# environode_display.net
KiCad netlist of a schematic drawn in EAGLE
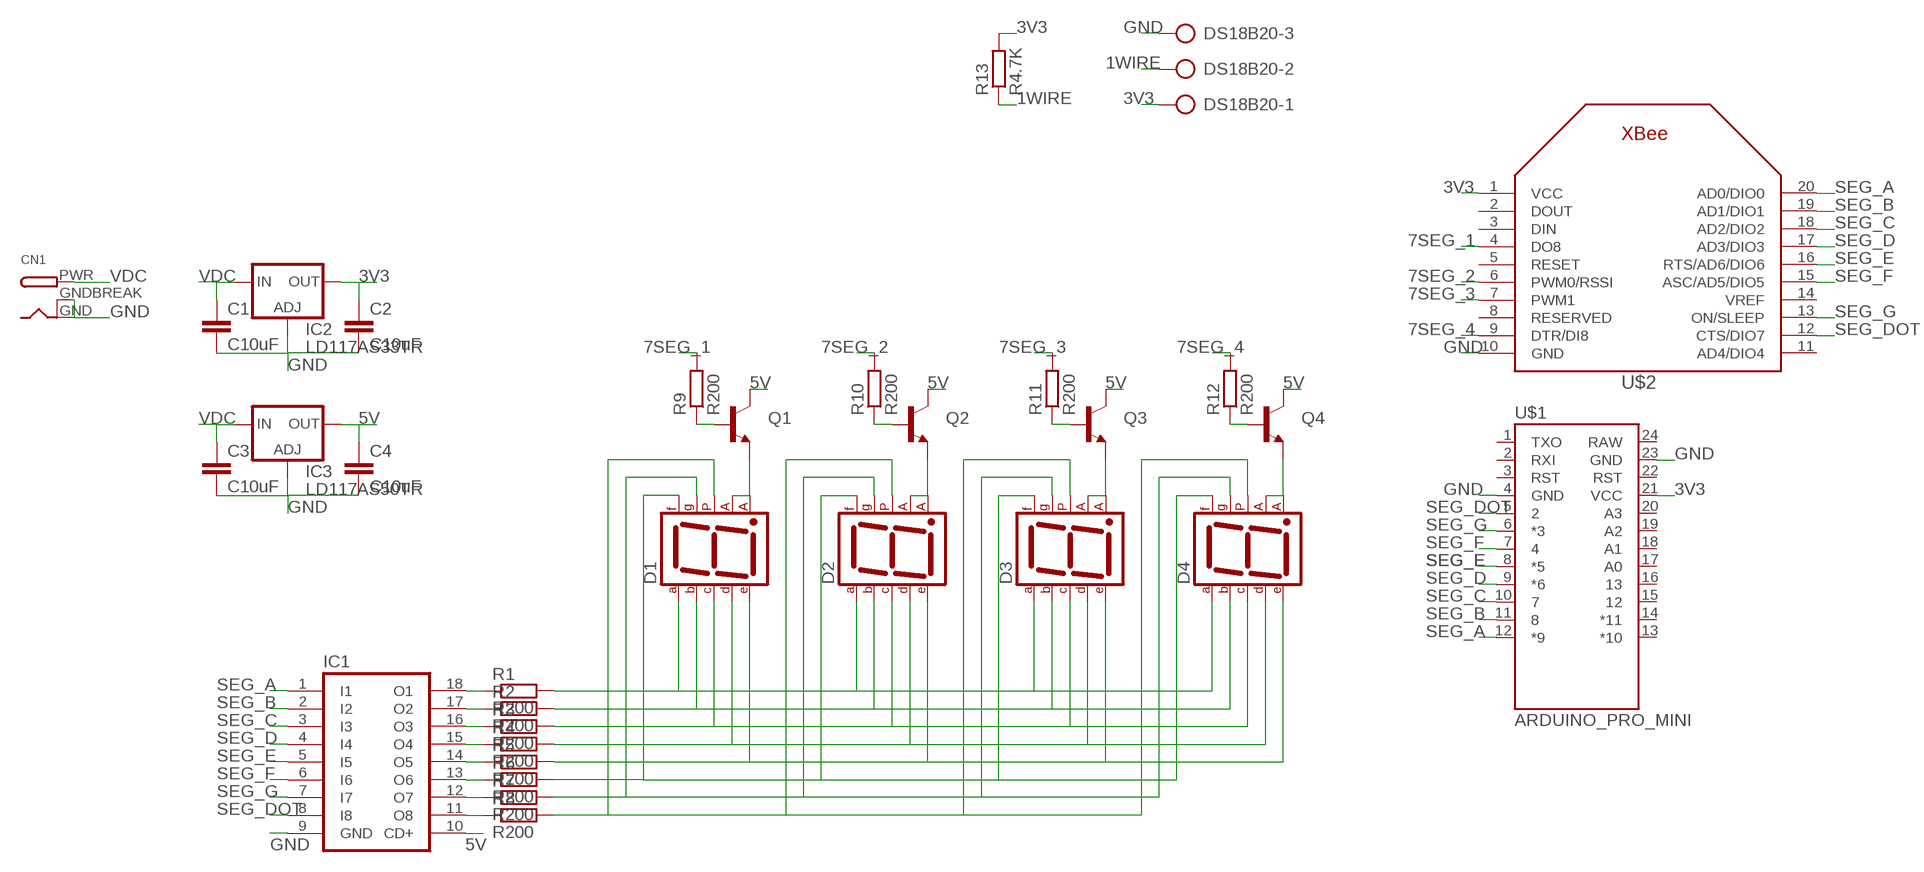
[diagram p0: schematic, sheet 1]

(export (version "E")
  (design (tool "Eeschema 10.0.6"))
  (components
    (comp (ref "C1")
      (value "C10uF")
      (footprint "eagle-import:C0805")
      (libsource (lib "eagle-import") (part "C-EUC0805"))
    )
    (comp (ref "C2")
      (value "C10uF")
      (footprint "eagle-import:C0805")
      (libsource (lib "eagle-import") (part "C-EUC0805"))
    )
    (comp (ref "C3")
      (value "C10uF")
      (footprint "eagle-import:C0805")
      (libsource (lib "eagle-import") (part "C-EUC0805"))
    )
    (comp (ref "C4")
      (value "C10uF")
      (footprint "eagle-import:C0805")
      (libsource (lib "eagle-import") (part "C-EUC0805"))
    )
    (comp (ref "CN1")
      (value "DCBARRELPTH")
      (footprint "eagle-import:DCJACK_2MM_PTH")
      (libsource (lib "eagle-import") (part "DCBARRELPTH"))
    )
    (comp (ref "D1")
      (value "7SEG-CA")
      (footprint "eagle-import:7SEG-13")
      (libsource (lib "eagle-import") (part "7SEG-CA"))
    )
    (comp (ref "D2")
      (value "7SEG-CA")
      (footprint "eagle-import:7SEG-13")
      (libsource (lib "eagle-import") (part "7SEG-CA"))
    )
    (comp (ref "D3")
      (value "7SEG-CA")
      (footprint "eagle-import:7SEG-13")
      (libsource (lib "eagle-import") (part "7SEG-CA"))
    )
    (comp (ref "D4")
      (value "7SEG-CA")
      (footprint "eagle-import:7SEG-13")
      (libsource (lib "eagle-import") (part "7SEG-CA"))
    )
    (comp (ref "DS18B20")
      (value "AK300/3")
      (footprint "eagle-import:AK300_3")
      (libsource (lib "eagle-import") (part "AK300/3"))
    )
    (comp (ref "IC1")
      (value "ULN2803A")
      (footprint "eagle-import:DIL18")
      (libsource (lib "eagle-import") (part "ULN2803A"))
    )
    (comp (ref "IC2")
      (value "LD117AS33TR")
      (footprint "eagle-import:SOT223")
      (libsource (lib "eagle-import") (part "LD117A?S33TR"))
    )
    (comp (ref "IC3")
      (value "LD117AS50TR")
      (footprint "eagle-import:SOT223")
      (libsource (lib "eagle-import") (part "LD117A?S50TR"))
    )
    (comp (ref "Q1")
      (value "TRANSISTOR_NPNP2N2222A")
      (footprint "eagle-import:TO-92")
      (libsource (lib "eagle-import") (part "TRANSISTOR_NPNP2N2222A"))
    )
    (comp (ref "Q2")
      (value "TRANSISTOR_NPNP2N2222A")
      (footprint "eagle-import:TO-92")
      (fields (field (name "PROD_ID") "TRANS-09536"))
      (libsource (lib "eagle-import") (part "TRANSISTOR_NPNP2N2222A"))
    )
    (comp (ref "Q3")
      (value "TRANSISTOR_NPNP2N2222A")
      (footprint "eagle-import:TO-92")
      (fields (field (name "PROD_ID") "TRANS-09536"))
      (libsource (lib "eagle-import") (part "TRANSISTOR_NPNP2N2222A"))
    )
    (comp (ref "Q4")
      (value "TRANSISTOR_NPNP2N2222A")
      (footprint "eagle-import:TO-92")
      (fields (field (name "PROD_ID") "TRANS-09536"))
      (libsource (lib "eagle-import") (part "TRANSISTOR_NPNP2N2222A"))
    )
    (comp (ref "R1")
      (value "R200")
      (footprint "eagle-import:0309V")
      (libsource (lib "eagle-import") (part "R-EU_0309/V"))
    )
    (comp (ref "R2")
      (value "R200")
      (footprint "eagle-import:0309V")
      (libsource (lib "eagle-import") (part "R-EU_0309/V"))
    )
    (comp (ref "R3")
      (value "R200")
      (footprint "eagle-import:0309V")
      (libsource (lib "eagle-import") (part "R-EU_0309/V"))
    )
    (comp (ref "R4")
      (value "R200")
      (footprint "eagle-import:0309V")
      (libsource (lib "eagle-import") (part "R-EU_0309/V"))
    )
    (comp (ref "R5")
      (value "R200")
      (footprint "eagle-import:0309V")
      (libsource (lib "eagle-import") (part "R-EU_0309/V"))
    )
    (comp (ref "R6")
      (value "R200")
      (footprint "eagle-import:0309V")
      (libsource (lib "eagle-import") (part "R-EU_0309/V"))
    )
    (comp (ref "R7")
      (value "R200")
      (footprint "eagle-import:0309V")
      (libsource (lib "eagle-import") (part "R-EU_0309/V"))
    )
    (comp (ref "R8")
      (value "R200")
      (footprint "eagle-import:0309V")
      (libsource (lib "eagle-import") (part "R-EU_0309/V"))
    )
    (comp (ref "R9")
      (value "R200")
      (footprint "eagle-import:0309V")
      (libsource (lib "eagle-import") (part "R-EU_0309/V"))
    )
    (comp (ref "R10")
      (value "R200")
      (footprint "eagle-import:0309V")
      (libsource (lib "eagle-import") (part "R-EU_0309/V"))
    )
    (comp (ref "R11")
      (value "R200")
      (footprint "eagle-import:0309V")
      (libsource (lib "eagle-import") (part "R-EU_0309/V"))
    )
    (comp (ref "R12")
      (value "R200")
      (footprint "eagle-import:0309V")
      (libsource (lib "eagle-import") (part "R-EU_0309/V"))
    )
    (comp (ref "R13")
      (value "R4.7K")
      (footprint "eagle-import:0309V")
      (libsource (lib "eagle-import") (part "R-EU_0309/V"))
    )
    (comp (ref "U$1")
      (value "ARDUINO_PRO_MINI")
      (footprint "eagle-import:ARDUINO_PRO_MINI")
      (libsource (lib "eagle-import") (part "ARDUINO_PRO_MINI"))
    )
    (comp (ref "U$2")
      (value "XBEE")
      (footprint "eagle-import:XBEE")
      (libsource (lib "eagle-import") (part "XBEE"))
    )
  )
  (nets
    (net (code "1") (name "/1WIRE") (class "Default")
      (node (ref "DS18B20") (pin "2") (pinfunction "KL_2") (pintype "passive"))
      (node (ref "R13") (pin "1") (pinfunction "1_1") (pintype "passive"))
    )
    (net (code "2") (name "/3V3") (class "Default")
      (node (ref "C2") (pin "1") (pinfunction "1_1") (pintype "passive"))
      (node (ref "DS18B20") (pin "1") (pinfunction "KL_1") (pintype "passive"))
      (node (ref "IC2") (pin "4") (pinfunction "OUT_4") (pintype "passive"))
      (node (ref "R13") (pin "2") (pinfunction "2_2") (pintype "passive"))
      (node (ref "U$1") (pin "21") (pinfunction "VCC_21") (pintype "bidirectional"))
      (node (ref "U$2") (pin "1") (pinfunction "VCC_1") (pintype "power_in"))
    )
    (net (code "3") (name "/5V") (class "Default")
      (node (ref "C4") (pin "1") (pinfunction "1_1") (pintype "passive"))
      (node (ref "IC1") (pin "10") (pinfunction "CD+_10") (pintype "passive"))
      (node (ref "IC3") (pin "4") (pinfunction "OUT_4") (pintype "passive"))
      (node (ref "Q1") (pin "1") (pinfunction "C_1") (pintype "passive"))
      (node (ref "Q2") (pin "1") (pinfunction "C_1") (pintype "passive"))
      (node (ref "Q3") (pin "1") (pinfunction "C_1") (pintype "passive"))
      (node (ref "Q4") (pin "1") (pinfunction "C_1") (pintype "passive"))
    )
    (net (code "4") (name "/7SEG_1") (class "Default")
      (node (ref "R9") (pin "2") (pinfunction "2_2") (pintype "passive"))
      (node (ref "U$2") (pin "4") (pinfunction "DO8_4") (pintype "output"))
    )
    (net (code "5") (name "/7SEG_2") (class "Default")
      (node (ref "R10") (pin "2") (pinfunction "2_2") (pintype "passive"))
      (node (ref "U$2") (pin "6") (pinfunction "PWM0/RSSI_6") (pintype "output"))
    )
    (net (code "6") (name "/7SEG_3") (class "Default")
      (node (ref "R11") (pin "2") (pinfunction "2_2") (pintype "passive"))
      (node (ref "U$2") (pin "7") (pinfunction "PWM1_7") (pintype "output"))
    )
    (net (code "7") (name "/7SEG_4") (class "Default")
      (node (ref "R12") (pin "2") (pinfunction "2_2") (pintype "passive"))
      (node (ref "U$2") (pin "9") (pinfunction "DTR/DI8_9") (pintype "input"))
    )
    (net (code "8") (name "/GND") (class "Default")
      (node (ref "C1") (pin "2") (pinfunction "2_2") (pintype "passive"))
      (node (ref "C2") (pin "2") (pinfunction "2_2") (pintype "passive"))
      (node (ref "C3") (pin "2") (pinfunction "2_2") (pintype "passive"))
      (node (ref "C4") (pin "2") (pinfunction "2_2") (pintype "passive"))
      (node (ref "CN1") (pin "GND") (pinfunction "GND_GND") (pintype "power_in"))
      (node (ref "CN1") (pin "GNDBREAK") (pinfunction "GNDBREAK_GNDBREAK") (pintype "power_in"))
      (node (ref "DS18B20") (pin "3") (pinfunction "KL_3") (pintype "passive"))
      (node (ref "IC1") (pin "9") (pinfunction "GND_9") (pintype "power_in"))
      (node (ref "IC2") (pin "1") (pinfunction "ADJ_1") (pintype "input"))
      (node (ref "IC3") (pin "1") (pinfunction "ADJ_1") (pintype "input"))
      (node (ref "U$1") (pin "23") (pinfunction "GND_23") (pintype "bidirectional"))
      (node (ref "U$1") (pin "4") (pinfunction "GND_4") (pintype "bidirectional"))
      (node (ref "U$2") (pin "10") (pinfunction "GND_10") (pintype "power_in"))
    )
    (net (code "9") (name "/SEG_A") (class "Default")
      (node (ref "IC1") (pin "1") (pinfunction "I1_1") (pintype "input"))
      (node (ref "U$1") (pin "12") (pinfunction "*9_12") (pintype "bidirectional"))
      (node (ref "U$2") (pin "20") (pinfunction "AD0/DIO0_20") (pintype "bidirectional"))
    )
    (net (code "10") (name "/SEG_B") (class "Default")
      (node (ref "IC1") (pin "2") (pinfunction "I2_2") (pintype "input"))
      (node (ref "U$1") (pin "11") (pinfunction "8_11") (pintype "bidirectional"))
      (node (ref "U$2") (pin "19") (pinfunction "AD1/DIO1_19") (pintype "bidirectional"))
    )
    (net (code "11") (name "/SEG_C") (class "Default")
      (node (ref "IC1") (pin "3") (pinfunction "I3_3") (pintype "input"))
      (node (ref "U$1") (pin "10") (pinfunction "7_10") (pintype "bidirectional"))
      (node (ref "U$2") (pin "18") (pinfunction "AD2/DIO2_18") (pintype "bidirectional"))
    )
    (net (code "12") (name "/SEG_D") (class "Default")
      (node (ref "IC1") (pin "4") (pinfunction "I4_4") (pintype "input"))
      (node (ref "U$1") (pin "9") (pinfunction "*6_9") (pintype "bidirectional"))
      (node (ref "U$2") (pin "17") (pinfunction "AD3/DIO3_17") (pintype "bidirectional"))
    )
    (net (code "13") (name "/SEG_DOT") (class "Default")
      (node (ref "IC1") (pin "8") (pinfunction "I8_8") (pintype "input"))
      (node (ref "U$1") (pin "5") (pinfunction "2_5") (pintype "bidirectional"))
      (node (ref "U$2") (pin "12") (pinfunction "CTS/DIO7_12") (pintype "bidirectional"))
    )
    (net (code "14") (name "/SEG_E") (class "Default")
      (node (ref "IC1") (pin "5") (pinfunction "I5_5") (pintype "input"))
      (node (ref "U$1") (pin "8") (pinfunction "*5_8") (pintype "bidirectional"))
      (node (ref "U$2") (pin "16") (pinfunction "RTS/AD6/DIO6_16") (pintype "bidirectional"))
    )
    (net (code "15") (name "/SEG_F") (class "Default")
      (node (ref "IC1") (pin "6") (pinfunction "I6_6") (pintype "input"))
      (node (ref "U$1") (pin "7") (pinfunction "4_7") (pintype "bidirectional"))
      (node (ref "U$2") (pin "15") (pinfunction "ASC/AD5/DIO5_15") (pintype "bidirectional"))
    )
    (net (code "16") (name "/SEG_G") (class "Default")
      (node (ref "IC1") (pin "7") (pinfunction "I7_7") (pintype "input"))
      (node (ref "U$1") (pin "6") (pinfunction "*3_6") (pintype "bidirectional"))
      (node (ref "U$2") (pin "13") (pinfunction "ON/SLEEP_13") (pintype "output"))
    )
    (net (code "17") (name "/VDC") (class "Default")
      (node (ref "C1") (pin "1") (pinfunction "1_1") (pintype "passive"))
      (node (ref "C3") (pin "1") (pinfunction "1_1") (pintype "passive"))
      (node (ref "CN1") (pin "PWR") (pinfunction "PWR_PWR") (pintype "power_in"))
      (node (ref "IC2") (pin "3") (pinfunction "IN_3") (pintype "input"))
      (node (ref "IC3") (pin "3") (pinfunction "IN_3") (pintype "input"))
    )
    (net (code "18") (name "Net-(D1-A)") (class "Default")
      (node (ref "D1") (pin "7") (pinfunction "A_7") (pintype "passive"))
      (node (ref "D2") (pin "7") (pinfunction "A_7") (pintype "passive"))
      (node (ref "D3") (pin "7") (pinfunction "A_7") (pintype "passive"))
      (node (ref "D4") (pin "7") (pinfunction "A_7") (pintype "passive"))
      (node (ref "R1") (pin "2") (pinfunction "2_2") (pintype "passive"))
    )
    (net (code "19") (name "Net-(D1-B)") (class "Default")
      (node (ref "D1") (pin "6") (pinfunction "B_6") (pintype "passive"))
      (node (ref "D2") (pin "6") (pinfunction "B_6") (pintype "passive"))
      (node (ref "D3") (pin "6") (pinfunction "B_6") (pintype "passive"))
      (node (ref "D4") (pin "6") (pinfunction "B_6") (pintype "passive"))
      (node (ref "R2") (pin "2") (pinfunction "2_2") (pintype "passive"))
    )
    (net (code "20") (name "Net-(D1-C)") (class "Default")
      (node (ref "D1") (pin "4") (pinfunction "C_4") (pintype "passive"))
      (node (ref "D2") (pin "4") (pinfunction "C_4") (pintype "passive"))
      (node (ref "D3") (pin "4") (pinfunction "C_4") (pintype "passive"))
      (node (ref "D4") (pin "4") (pinfunction "C_4") (pintype "passive"))
      (node (ref "R3") (pin "2") (pinfunction "2_2") (pintype "passive"))
    )
    (net (code "21") (name "Net-(D1-CA1)") (class "Default")
      (node (ref "D1") (pin "3") (pinfunction "CA1_3") (pintype "passive"))
      (node (ref "D1") (pin "8") (pinfunction "CA2_8") (pintype "passive"))
      (node (ref "Q1") (pin "3") (pinfunction "E_3") (pintype "passive"))
    )
    (net (code "22") (name "Net-(D1-D)") (class "Default")
      (node (ref "D1") (pin "2") (pinfunction "D_2") (pintype "passive"))
      (node (ref "D2") (pin "2") (pinfunction "D_2") (pintype "passive"))
      (node (ref "D3") (pin "2") (pinfunction "D_2") (pintype "passive"))
      (node (ref "D4") (pin "2") (pinfunction "D_2") (pintype "passive"))
      (node (ref "R4") (pin "2") (pinfunction "2_2") (pintype "passive"))
    )
    (net (code "23") (name "Net-(D1-DP)") (class "Default")
      (node (ref "D1") (pin "5") (pinfunction "DP_5") (pintype "passive"))
      (node (ref "D2") (pin "5") (pinfunction "DP_5") (pintype "passive"))
      (node (ref "D3") (pin "5") (pinfunction "DP_5") (pintype "passive"))
      (node (ref "D4") (pin "5") (pinfunction "DP_5") (pintype "passive"))
      (node (ref "R8") (pin "2") (pinfunction "2_2") (pintype "passive"))
    )
    (net (code "24") (name "Net-(D1-E)") (class "Default")
      (node (ref "D1") (pin "1") (pinfunction "E_1") (pintype "passive"))
      (node (ref "D2") (pin "1") (pinfunction "E_1") (pintype "passive"))
      (node (ref "D3") (pin "1") (pinfunction "E_1") (pintype "passive"))
      (node (ref "D4") (pin "1") (pinfunction "E_1") (pintype "passive"))
      (node (ref "R5") (pin "2") (pinfunction "2_2") (pintype "passive"))
    )
    (net (code "25") (name "Net-(D1-F)") (class "Default")
      (node (ref "D1") (pin "9") (pinfunction "F_9") (pintype "passive"))
      (node (ref "D2") (pin "9") (pinfunction "F_9") (pintype "passive"))
      (node (ref "D3") (pin "9") (pinfunction "F_9") (pintype "passive"))
      (node (ref "D4") (pin "9") (pinfunction "F_9") (pintype "passive"))
      (node (ref "R6") (pin "2") (pinfunction "2_2") (pintype "passive"))
    )
    (net (code "26") (name "Net-(D1-G)") (class "Default")
      (node (ref "D1") (pin "10") (pinfunction "G_10") (pintype "passive"))
      (node (ref "D2") (pin "10") (pinfunction "G_10") (pintype "passive"))
      (node (ref "D3") (pin "10") (pinfunction "G_10") (pintype "passive"))
      (node (ref "D4") (pin "10") (pinfunction "G_10") (pintype "passive"))
      (node (ref "R7") (pin "2") (pinfunction "2_2") (pintype "passive"))
    )
    (net (code "27") (name "Net-(D2-CA1)") (class "Default")
      (node (ref "D2") (pin "3") (pinfunction "CA1_3") (pintype "passive"))
      (node (ref "D2") (pin "8") (pinfunction "CA2_8") (pintype "passive"))
      (node (ref "Q2") (pin "3") (pinfunction "E_3") (pintype "passive"))
    )
    (net (code "28") (name "Net-(D3-CA1)") (class "Default")
      (node (ref "D3") (pin "3") (pinfunction "CA1_3") (pintype "passive"))
      (node (ref "D3") (pin "8") (pinfunction "CA2_8") (pintype "passive"))
      (node (ref "Q3") (pin "3") (pinfunction "E_3") (pintype "passive"))
    )
    (net (code "29") (name "Net-(D4-CA1)") (class "Default")
      (node (ref "D4") (pin "3") (pinfunction "CA1_3") (pintype "passive"))
      (node (ref "D4") (pin "8") (pinfunction "CA2_8") (pintype "passive"))
      (node (ref "Q4") (pin "3") (pinfunction "E_3") (pintype "passive"))
    )
    (net (code "30") (name "Net-(IC1-O1)") (class "Default")
      (node (ref "IC1") (pin "18") (pinfunction "O1_18") (pintype "open_collector"))
      (node (ref "R1") (pin "1") (pinfunction "1_1") (pintype "passive"))
    )
    (net (code "31") (name "Net-(IC1-O2)") (class "Default")
      (node (ref "IC1") (pin "17") (pinfunction "O2_17") (pintype "open_collector"))
      (node (ref "R2") (pin "1") (pinfunction "1_1") (pintype "passive"))
    )
    (net (code "32") (name "Net-(IC1-O3)") (class "Default")
      (node (ref "IC1") (pin "16") (pinfunction "O3_16") (pintype "open_collector"))
      (node (ref "R3") (pin "1") (pinfunction "1_1") (pintype "passive"))
    )
    (net (code "33") (name "Net-(IC1-O4)") (class "Default")
      (node (ref "IC1") (pin "15") (pinfunction "O4_15") (pintype "open_collector"))
      (node (ref "R4") (pin "1") (pinfunction "1_1") (pintype "passive"))
    )
    (net (code "34") (name "Net-(IC1-O5)") (class "Default")
      (node (ref "IC1") (pin "14") (pinfunction "O5_14") (pintype "open_collector"))
      (node (ref "R5") (pin "1") (pinfunction "1_1") (pintype "passive"))
    )
    (net (code "35") (name "Net-(IC1-O6)") (class "Default")
      (node (ref "IC1") (pin "13") (pinfunction "O6_13") (pintype "open_collector"))
      (node (ref "R6") (pin "1") (pinfunction "1_1") (pintype "passive"))
    )
    (net (code "36") (name "Net-(IC1-O7)") (class "Default")
      (node (ref "IC1") (pin "12") (pinfunction "O7_12") (pintype "open_collector"))
      (node (ref "R7") (pin "1") (pinfunction "1_1") (pintype "passive"))
    )
    (net (code "37") (name "Net-(IC1-O8)") (class "Default")
      (node (ref "IC1") (pin "11") (pinfunction "O8_11") (pintype "open_collector"))
      (node (ref "R8") (pin "1") (pinfunction "1_1") (pintype "passive"))
    )
    (net (code "38") (name "Net-(Q1-B)") (class "Default")
      (node (ref "Q1") (pin "2") (pinfunction "B_2") (pintype "passive"))
      (node (ref "R9") (pin "1") (pinfunction "1_1") (pintype "passive"))
    )
    (net (code "39") (name "Net-(Q2-B)") (class "Default")
      (node (ref "Q2") (pin "2") (pinfunction "B_2") (pintype "passive"))
      (node (ref "R10") (pin "1") (pinfunction "1_1") (pintype "passive"))
    )
    (net (code "40") (name "Net-(Q3-B)") (class "Default")
      (node (ref "Q3") (pin "2") (pinfunction "B_2") (pintype "passive"))
      (node (ref "R11") (pin "1") (pinfunction "1_1") (pintype "passive"))
    )
    (net (code "41") (name "Net-(Q4-B)") (class "Default")
      (node (ref "Q4") (pin "2") (pinfunction "B_2") (pintype "passive"))
      (node (ref "R12") (pin "1") (pinfunction "1_1") (pintype "passive"))
    )
    (net (code "42") (name "unconnected-(U$1-*10-Pad13)") (class "Default")
      (node (ref "U$1") (pin "13") (pinfunction "*10_13") (pintype "bidirectional"))
    )
    (net (code "43") (name "unconnected-(U$1-*11-Pad14)") (class "Default")
      (node (ref "U$1") (pin "14") (pinfunction "*11_14") (pintype "bidirectional"))
    )
    (net (code "44") (name "unconnected-(U$1-12-Pad15)") (class "Default")
      (node (ref "U$1") (pin "15") (pinfunction "12_15") (pintype "bidirectional"))
    )
    (net (code "45") (name "unconnected-(U$1-13-Pad16)") (class "Default")
      (node (ref "U$1") (pin "16") (pinfunction "13_16") (pintype "bidirectional"))
    )
    (net (code "46") (name "unconnected-(U$1-A0-Pad17)") (class "Default")
      (node (ref "U$1") (pin "17") (pinfunction "A0_17") (pintype "bidirectional"))
    )
    (net (code "47") (name "unconnected-(U$1-A1-Pad18)") (class "Default")
      (node (ref "U$1") (pin "18") (pinfunction "A1_18") (pintype "bidirectional"))
    )
    (net (code "48") (name "unconnected-(U$1-A2-Pad19)") (class "Default")
      (node (ref "U$1") (pin "19") (pinfunction "A2_19") (pintype "bidirectional"))
    )
    (net (code "49") (name "unconnected-(U$1-A3-Pad20)") (class "Default")
      (node (ref "U$1") (pin "20") (pinfunction "A3_20") (pintype "bidirectional"))
    )
    (net (code "50") (name "unconnected-(U$1-RAW-Pad24)") (class "Default")
      (node (ref "U$1") (pin "24") (pinfunction "RAW_24") (pintype "bidirectional"))
    )
    (net (code "51") (name "unconnected-(U$1-RST-Pad3)") (class "Default")
      (node (ref "U$1") (pin "3") (pinfunction "RST_3") (pintype "bidirectional"))
    )
    (net (code "52") (name "unconnected-(U$1-RST-Pad22)") (class "Default")
      (node (ref "U$1") (pin "22") (pinfunction "RST_22") (pintype "bidirectional"))
    )
    (net (code "53") (name "unconnected-(U$1-RXI-Pad2)") (class "Default")
      (node (ref "U$1") (pin "2") (pinfunction "RXI_2") (pintype "bidirectional"))
    )
    (net (code "54") (name "unconnected-(U$1-TXO-Pad1)") (class "Default")
      (node (ref "U$1") (pin "1") (pinfunction "TXO_1") (pintype "bidirectional"))
    )
    (net (code "55") (name "unconnected-(U$2-AD4{slash}DIO4-Pad11)") (class "Default")
      (node (ref "U$2") (pin "11") (pinfunction "AD4/DIO4_11") (pintype "bidirectional"))
    )
    (net (code "56") (name "unconnected-(U$2-DIN-Pad3)") (class "Default")
      (node (ref "U$2") (pin "3") (pinfunction "DIN_3") (pintype "input"))
    )
    (net (code "57") (name "unconnected-(U$2-DOUT-Pad2)") (class "Default")
      (node (ref "U$2") (pin "2") (pinfunction "DOUT_2") (pintype "output"))
    )
    (net (code "58") (name "unconnected-(U$2-RESERVED-Pad8)") (class "Default")
      (node (ref "U$2") (pin "8") (pinfunction "RESERVED_8") (pintype "no_connect"))
    )
    (net (code "59") (name "unconnected-(U$2-RESET-Pad5)") (class "Default")
      (node (ref "U$2") (pin "5") (pinfunction "RESET_5") (pintype "input"))
    )
    (net (code "60") (name "unconnected-(U$2-VREF-Pad14)") (class "Default")
      (node (ref "U$2") (pin "14") (pinfunction "VREF_14") (pintype "input"))
    )
  )
)
